# CAN.net
KiCad netlist of a schematic drawn in Altium Designer
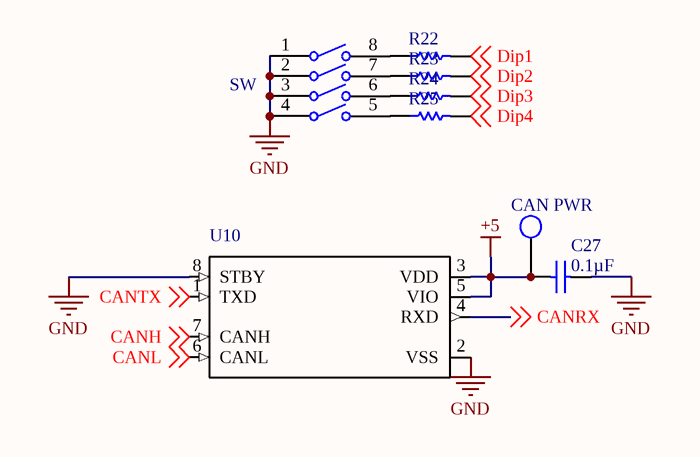
[diagram p0: CAN.SchDoc]

(export (version "E")
  (design (tool "Eeschema 10.0.6"))
  (components
    (comp (ref "C27")
      (value "Capacitor 0805")
      (footprint "Cap 0805")
      (description "Standard Capacitor")
      (fields (field (name "MANUFACTURER") "AVX") (field (name "CAPACITANCE") "0.1µF"))
      (libsource (lib "Standard Cap") (part "Capacitor 0805"))
    )
    (comp (ref "CAN PWR")
      (value "Test Point")
      (footprint "Test Point Through-hole")
      (libsource (lib "Husky Robotics Standard Library 2019-2020") (part "Test Point"))
    )
    (comp (ref "R22")
      (value "Resistor 0805")
      (footprint "RESC0805(2012)_N")
      (description "Generic 0805 Resistor")
      (fields (field (name "TOLERANCE") "5 %") (field (name "POWER") "0.125 W"))
      (libsource (lib "Husky Robotics Standard Library 2019-2020") (part "Resistor 0805"))
    )
    (comp (ref "R23")
      (value "Resistor 0805")
      (footprint "RESC0805(2012)_N")
      (description "Generic 0805 Resistor")
      (fields (field (name "TOLERANCE") "5 %") (field (name "POWER") "0.125 W"))
      (libsource (lib "Husky Robotics Standard Library 2019-2020") (part "Resistor 0805"))
    )
    (comp (ref "R24")
      (value "Resistor 0805")
      (footprint "RESC0805(2012)_N")
      (description "Generic 0805 Resistor")
      (fields (field (name "TOLERANCE") "5 %") (field (name "POWER") "0.125 W"))
      (libsource (lib "Husky Robotics Standard Library 2019-2020") (part "Resistor 0805"))
    )
    (comp (ref "R25")
      (value "Resistor 0805")
      (footprint "RESC0805(2012)_N")
      (description "Generic 0805 Resistor")
      (fields (field (name "TOLERANCE") "5 %") (field (name "POWER") "0.125 W"))
      (libsource (lib "Husky Robotics Standard Library 2019-2020") (part "Resistor 0805"))
    )
    (comp (ref "SW")
      (value "TDA04H0SB1")
      (footprint "CKCP-TDA04H0SB1R_V")
      (fields (field (name "DIGI-KEY_PART_NUMBER") "CKN9065-ND"))
      (libsource (lib "Husky Robotics Standard Library 2019-2020") (part "Dip Switch Array SMD Half-Pitch"))
    )
    (comp (ref "U10")
      (value "MCP2562-E/SN")
      (footprint "SOIC127P600X175-8N")
      (description "Microchip MCP2562-E/SN, CAN Transceiver 1MBps 1-channel IEC 61000-4-2, 8-Pin SOIC")
      (fields (field (name "MF") "Microchip") (field (name "DIGI-KEY_PART_NUMBER") "MCP2562T-E/SNCT-ND"))
      (libsource (lib "Husky Robotics Standard Library 2019-2020") (part "CAN Tranceiver"))
    )
  )
  (nets
    (net (code "1") (name "+5") (class "Default")
      (node (ref "C27") (pin "1") (pinfunction "1_1") (pintype "passive"))
      (node (ref "CAN PWR") (pin "1") (pinfunction "1_1") (pintype "passive"))
      (node (ref "U10") (pin "3") (pinfunction "VDD_3") (pintype "power_in"))
      (node (ref "U10") (pin "5") (pinfunction "VIO_5") (pintype "power_in"))
    )
    (net (code "2") (name "CANH") (class "Default")
      (node (ref "U10") (pin "7") (pinfunction "CANH_7") (pintype "input"))
    )
    (net (code "3") (name "CANL") (class "Default")
      (node (ref "U10") (pin "6") (pinfunction "CANL_6") (pintype "input"))
    )
    (net (code "4") (name "CANRX") (class "Default")
      (node (ref "U10") (pin "4") (pinfunction "RXD_4") (pintype "output"))
    )
    (net (code "5") (name "CANTX") (class "Default")
      (node (ref "U10") (pin "1") (pinfunction "TXD_1") (pintype "input"))
    )
    (net (code "6") (name "Dip1") (class "Default")
      (node (ref "R22") (pin "2") (pinfunction "2_2") (pintype "passive"))
    )
    (net (code "7") (name "Dip2") (class "Default")
      (node (ref "R23") (pin "2") (pinfunction "2_2") (pintype "passive"))
    )
    (net (code "8") (name "Dip3") (class "Default")
      (node (ref "R24") (pin "2") (pinfunction "2_2") (pintype "passive"))
    )
    (net (code "9") (name "Dip4") (class "Default")
      (node (ref "R25") (pin "2") (pinfunction "2_2") (pintype "passive"))
    )
    (net (code "10") (name "GND") (class "Default")
      (node (ref "C27") (pin "2") (pinfunction "2_2") (pintype "passive"))
      (node (ref "SW") (pin "1") (pinfunction "1_1") (pintype "passive"))
      (node (ref "SW") (pin "2") (pinfunction "2_2") (pintype "passive"))
      (node (ref "SW") (pin "3") (pinfunction "3_3") (pintype "passive"))
      (node (ref "SW") (pin "4") (pinfunction "4_4") (pintype "passive"))
      (node (ref "U10") (pin "2") (pinfunction "VSS_2") (pintype "power_in"))
      (node (ref "U10") (pin "8") (pinfunction "STBY_8") (pintype "input"))
    )
    (net (code "11") (name "Net-(R22-Pad1)") (class "Default")
      (node (ref "R22") (pin "1") (pinfunction "1_1") (pintype "passive"))
      (node (ref "SW") (pin "8") (pinfunction "8_8") (pintype "passive"))
    )
    (net (code "12") (name "Net-(R23-Pad1)") (class "Default")
      (node (ref "R23") (pin "1") (pinfunction "1_1") (pintype "passive"))
      (node (ref "SW") (pin "7") (pinfunction "7_7") (pintype "passive"))
    )
    (net (code "13") (name "Net-(R24-Pad1)") (class "Default")
      (node (ref "R24") (pin "1") (pinfunction "1_1") (pintype "passive"))
      (node (ref "SW") (pin "6") (pinfunction "6_6") (pintype "passive"))
    )
    (net (code "14") (name "Net-(R25-Pad1)") (class "Default")
      (node (ref "R25") (pin "1") (pinfunction "1_1") (pintype "passive"))
      (node (ref "SW") (pin "5") (pinfunction "5_5") (pintype "passive"))
    )
  )
)
